# tinydie.net
KiCad netlist of a schematic drawn in EAGLE
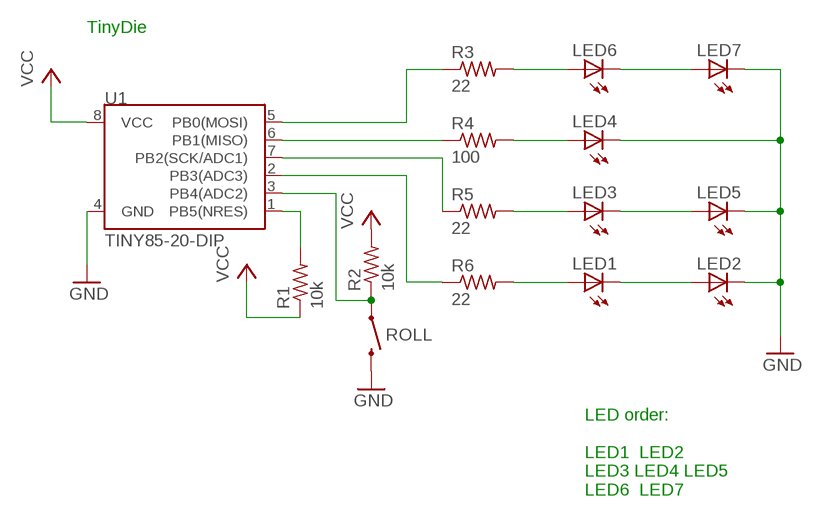
[diagram p0: schematic, sheet 1]

(export (version "E")
  (design (tool "Eeschema 10.0.6"))
  (components
    (comp (ref "LED1")
      (value "LED3MM")
      (footprint "eagle-import:LED3MM")
      (libsource (lib "eagle-import") (part "LED3MM"))
    )
    (comp (ref "LED2")
      (value "LED3MM")
      (footprint "eagle-import:LED3MM")
      (libsource (lib "eagle-import") (part "LED3MM"))
    )
    (comp (ref "LED3")
      (value "LED3MM")
      (footprint "eagle-import:LED3MM")
      (libsource (lib "eagle-import") (part "LED3MM"))
    )
    (comp (ref "LED4")
      (value "LED3MM")
      (footprint "eagle-import:LED3MM")
      (libsource (lib "eagle-import") (part "LED3MM"))
    )
    (comp (ref "LED5")
      (value "LED3MM")
      (footprint "eagle-import:LED3MM")
      (libsource (lib "eagle-import") (part "LED3MM"))
    )
    (comp (ref "LED6")
      (value "LED3MM")
      (footprint "eagle-import:LED3MM")
      (libsource (lib "eagle-import") (part "LED3MM"))
    )
    (comp (ref "LED7")
      (value "LED3MM")
      (footprint "eagle-import:LED3MM")
      (libsource (lib "eagle-import") (part "LED3MM"))
    )
    (comp (ref "R1")
      (value "10k")
      (footprint "eagle-import:0207_7")
      (libsource (lib "eagle-import") (part "R-US_0207/7"))
    )
    (comp (ref "R2")
      (value "10k")
      (footprint "eagle-import:0207_7")
      (libsource (lib "eagle-import") (part "R-US_0207/7"))
    )
    (comp (ref "R3")
      (value "22")
      (footprint "eagle-import:0207_7")
      (libsource (lib "eagle-import") (part "R-US_0207/7"))
    )
    (comp (ref "R4")
      (value "100")
      (footprint "eagle-import:0207_7")
      (libsource (lib "eagle-import") (part "R-US_0207/7"))
    )
    (comp (ref "R5")
      (value "22")
      (footprint "eagle-import:0207_7")
      (libsource (lib "eagle-import") (part "R-US_0207/7"))
    )
    (comp (ref "R6")
      (value "22")
      (footprint "eagle-import:0207_7")
      (libsource (lib "eagle-import") (part "R-US_0207/7"))
    )
    (comp (ref "ROLL")
      (value "SWITCH-MOMENTARY-2")
      (footprint "eagle-import:TACTILE_SWITCH_TALL")
      (libsource (lib "eagle-import") (part "SWITCH-MOMENTARY-2"))
    )
    (comp (ref "U1")
      (value "TINY85-20-DIP")
      (footprint "eagle-import:DIP08")
      (libsource (lib "eagle-import") (part "ATTINY45TINY85-20-DIP"))
    )
  )
  (nets
    (net (code "1") (name "GND") (class "Default")
      (node (ref "LED2") (pin "K") (pinfunction "C_K") (pintype "passive"))
      (node (ref "LED4") (pin "K") (pinfunction "C_K") (pintype "passive"))
      (node (ref "LED5") (pin "K") (pinfunction "C_K") (pintype "passive"))
      (node (ref "LED7") (pin "K") (pinfunction "C_K") (pintype "passive"))
      (node (ref "ROLL") (pin "B2") (pinfunction "2_B2") (pintype "passive"))
      (node (ref "U1") (pin "4") (pinfunction "GND_4") (pintype "bidirectional"))
    )
    (net (code "2") (name "Net-(LED1-C)") (class "Default")
      (node (ref "LED1") (pin "K") (pinfunction "C_K") (pintype "passive"))
      (node (ref "LED2") (pin "A") (pinfunction "A_A") (pintype "passive"))
    )
    (net (code "3") (name "Net-(LED1-PadA)") (class "Default")
      (node (ref "LED1") (pin "A") (pinfunction "A_A") (pintype "passive"))
      (node (ref "R6") (pin "2") (pinfunction "2_2") (pintype "passive"))
    )
    (net (code "4") (name "Net-(LED3-C)") (class "Default")
      (node (ref "LED3") (pin "K") (pinfunction "C_K") (pintype "passive"))
      (node (ref "LED5") (pin "A") (pinfunction "A_A") (pintype "passive"))
    )
    (net (code "5") (name "Net-(LED3-PadA)") (class "Default")
      (node (ref "LED3") (pin "A") (pinfunction "A_A") (pintype "passive"))
      (node (ref "R5") (pin "2") (pinfunction "2_2") (pintype "passive"))
    )
    (net (code "6") (name "Net-(LED4-PadA)") (class "Default")
      (node (ref "LED4") (pin "A") (pinfunction "A_A") (pintype "passive"))
      (node (ref "R4") (pin "2") (pinfunction "2_2") (pintype "passive"))
    )
    (net (code "7") (name "Net-(LED6-C)") (class "Default")
      (node (ref "LED6") (pin "K") (pinfunction "C_K") (pintype "passive"))
      (node (ref "LED7") (pin "A") (pinfunction "A_A") (pintype "passive"))
    )
    (net (code "8") (name "Net-(LED6-PadA)") (class "Default")
      (node (ref "LED6") (pin "A") (pinfunction "A_A") (pintype "passive"))
      (node (ref "R3") (pin "2") (pinfunction "2_2") (pintype "passive"))
    )
    (net (code "9") (name "Net-(ROLL-1)") (class "Default")
      (node (ref "R2") (pin "1") (pinfunction "1_1") (pintype "passive"))
      (node (ref "ROLL") (pin "A2") (pinfunction "1_A2") (pintype "passive"))
      (node (ref "U1") (pin "3") (pinfunction "PB4(ADC2)_3") (pintype "bidirectional"))
    )
    (net (code "10") (name "Net-(U1-PB0(MOSI))") (class "Default")
      (node (ref "R3") (pin "1") (pinfunction "1_1") (pintype "passive"))
      (node (ref "U1") (pin "5") (pinfunction "PB0(MOSI)_5") (pintype "bidirectional"))
    )
    (net (code "11") (name "Net-(U1-PB1(MISO))") (class "Default")
      (node (ref "R4") (pin "1") (pinfunction "1_1") (pintype "passive"))
      (node (ref "U1") (pin "6") (pinfunction "PB1(MISO)_6") (pintype "bidirectional"))
    )
    (net (code "12") (name "Net-(U1-PB2(SCK{slash}ADC1))") (class "Default")
      (node (ref "R5") (pin "1") (pinfunction "1_1") (pintype "passive"))
      (node (ref "U1") (pin "7") (pinfunction "PB2(SCK/ADC1)_7") (pintype "bidirectional"))
    )
    (net (code "13") (name "Net-(U1-PB3(ADC3))") (class "Default")
      (node (ref "R6") (pin "1") (pinfunction "1_1") (pintype "passive"))
      (node (ref "U1") (pin "2") (pinfunction "PB3(ADC3)_2") (pintype "bidirectional"))
    )
    (net (code "14") (name "Net-(U1-PB5(NRES))") (class "Default")
      (node (ref "R1") (pin "2") (pinfunction "2_2") (pintype "passive"))
      (node (ref "U1") (pin "1") (pinfunction "PB5(NRES)_1") (pintype "bidirectional"))
    )
    (net (code "15") (name "VCC") (class "Default")
      (node (ref "R1") (pin "1") (pinfunction "1_1") (pintype "passive"))
      (node (ref "R2") (pin "2") (pinfunction "2_2") (pintype "passive"))
      (node (ref "U1") (pin "8") (pinfunction "VCC_8") (pintype "bidirectional"))
    )
  )
)
